# exp31dc.net
KiCad netlist of a schematic drawn in EAGLE
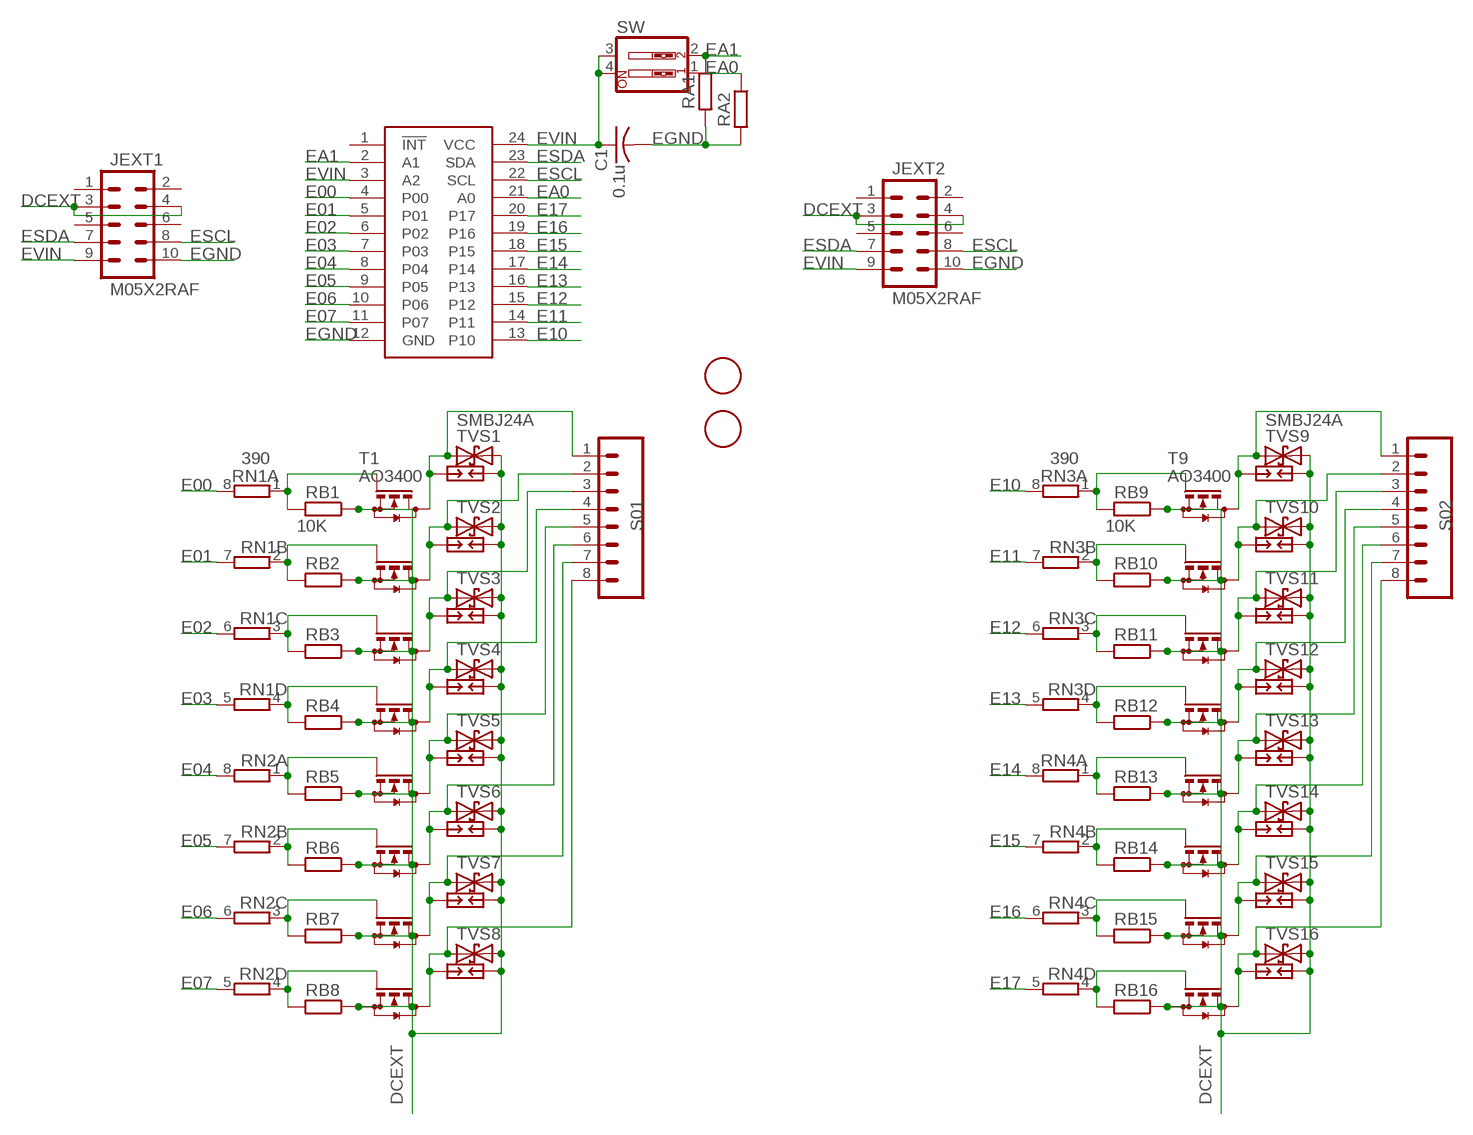
[diagram p0: schematic, sheet 1]

(export (version "E")
  (design (tool "Eeschema 10.0.6"))
  (components
    (comp (ref "C1")
      (value "0.1u")
      (footprint "eagle-import:C0603")
      (libsource (lib "eagle-import") (part "C-USC0603"))
    )
    (comp (ref "JEXT1")
      (value "M05X2RAF")
      (footprint "eagle-import:2X5-RAF")
      (libsource (lib "eagle-import") (part "M05X2RAF"))
    )
    (comp (ref "JEXT2")
      (value "M05X2RAF")
      (footprint "eagle-import:2X5-RAF")
      (libsource (lib "eagle-import") (part "M05X2RAF"))
    )
    (comp (ref "PCA9555")
      (value "PCA9555")
      (footprint "eagle-import:TSSOP24")
      (libsource (lib "eagle-import") (part "PCF8575TSSOP24"))
    )
    (comp (ref "RA1")
      (value "10K")
      (footprint "eagle-import:R0603")
      (libsource (lib "eagle-import") (part "R-EU_R0603"))
    )
    (comp (ref "RA2")
      (value "10K")
      (footprint "eagle-import:R0603")
      (libsource (lib "eagle-import") (part "R-EU_R0603"))
    )
    (comp (ref "RB1")
      (value "10K")
      (footprint "eagle-import:R0603")
      (libsource (lib "eagle-import") (part "R-EU_R0603"))
    )
    (comp (ref "RB2")
      (value "10K")
      (footprint "eagle-import:R0603")
      (libsource (lib "eagle-import") (part "R-EU_R0603"))
    )
    (comp (ref "RB3")
      (value "10K")
      (footprint "eagle-import:R0603")
      (libsource (lib "eagle-import") (part "R-EU_R0603"))
    )
    (comp (ref "RB4")
      (value "10K")
      (footprint "eagle-import:R0603")
      (libsource (lib "eagle-import") (part "R-EU_R0603"))
    )
    (comp (ref "RB5")
      (value "10K")
      (footprint "eagle-import:R0603")
      (libsource (lib "eagle-import") (part "R-EU_R0603"))
    )
    (comp (ref "RB6")
      (value "10K")
      (footprint "eagle-import:R0603")
      (libsource (lib "eagle-import") (part "R-EU_R0603"))
    )
    (comp (ref "RB7")
      (value "10K")
      (footprint "eagle-import:R0603")
      (libsource (lib "eagle-import") (part "R-EU_R0603"))
    )
    (comp (ref "RB8")
      (value "10K")
      (footprint "eagle-import:R0603")
      (libsource (lib "eagle-import") (part "R-EU_R0603"))
    )
    (comp (ref "RB9")
      (value "10K")
      (footprint "eagle-import:R0603")
      (libsource (lib "eagle-import") (part "R-EU_R0603"))
    )
    (comp (ref "RB10")
      (value "10K")
      (footprint "eagle-import:R0603")
      (libsource (lib "eagle-import") (part "R-EU_R0603"))
    )
    (comp (ref "RB11")
      (value "10K")
      (footprint "eagle-import:R0603")
      (libsource (lib "eagle-import") (part "R-EU_R0603"))
    )
    (comp (ref "RB12")
      (value "10K")
      (footprint "eagle-import:R0603")
      (libsource (lib "eagle-import") (part "R-EU_R0603"))
    )
    (comp (ref "RB13")
      (value "10K")
      (footprint "eagle-import:R0603")
      (libsource (lib "eagle-import") (part "R-EU_R0603"))
    )
    (comp (ref "RB14")
      (value "10K")
      (footprint "eagle-import:R0603")
      (libsource (lib "eagle-import") (part "R-EU_R0603"))
    )
    (comp (ref "RB15")
      (value "10K")
      (footprint "eagle-import:R0603")
      (libsource (lib "eagle-import") (part "R-EU_R0603"))
    )
    (comp (ref "RB16")
      (value "10K")
      (footprint "eagle-import:R0603")
      (libsource (lib "eagle-import") (part "R-EU_R0603"))
    )
    (comp (ref "RN1")
      (value "390")
      (footprint "eagle-import:EXB38V")
      (libsource (lib "eagle-import") (part "4R-NEXB38V"))
    )
    (comp (ref "RN2")
      (value "390")
      (footprint "eagle-import:EXB38V")
      (libsource (lib "eagle-import") (part "4R-NEXB38V"))
    )
    (comp (ref "RN3")
      (value "390")
      (footprint "eagle-import:EXB38V")
      (libsource (lib "eagle-import") (part "4R-NEXB38V"))
    )
    (comp (ref "RN4")
      (value "390")
      (footprint "eagle-import:EXB38V")
      (libsource (lib "eagle-import") (part "4R-NEXB38V"))
    )
    (comp (ref "S01")
      (value "M085MM-8")
      (footprint "eagle-import:SCREWTERMINAL-5MM-8")
      (libsource (lib "eagle-import") (part "M085MM-8"))
    )
    (comp (ref "S02")
      (value "M085MM-8")
      (footprint "eagle-import:SCREWTERMINAL-5MM-8")
      (libsource (lib "eagle-import") (part "M085MM-8"))
    )
    (comp (ref "SP1")
      (value "PCB-SGAP")
      (footprint "eagle-import:PCB-SGAP")
      (libsource (lib "eagle-import") (part "PCB-SGAP"))
    )
    (comp (ref "SP2")
      (value "PCB-SGAP")
      (footprint "eagle-import:PCB-SGAP")
      (libsource (lib "eagle-import") (part "PCB-SGAP"))
    )
    (comp (ref "SP3")
      (value "PCB-SGAP")
      (footprint "eagle-import:PCB-SGAP")
      (libsource (lib "eagle-import") (part "PCB-SGAP"))
    )
    (comp (ref "SP4")
      (value "PCB-SGAP")
      (footprint "eagle-import:PCB-SGAP")
      (libsource (lib "eagle-import") (part "PCB-SGAP"))
    )
    (comp (ref "SP5")
      (value "PCB-SGAP")
      (footprint "eagle-import:PCB-SGAP")
      (libsource (lib "eagle-import") (part "PCB-SGAP"))
    )
    (comp (ref "SP6")
      (value "PCB-SGAP")
      (footprint "eagle-import:PCB-SGAP")
      (libsource (lib "eagle-import") (part "PCB-SGAP"))
    )
    (comp (ref "SP7")
      (value "PCB-SGAP")
      (footprint "eagle-import:PCB-SGAP")
      (libsource (lib "eagle-import") (part "PCB-SGAP"))
    )
    (comp (ref "SP8")
      (value "PCB-SGAP")
      (footprint "eagle-import:PCB-SGAP")
      (libsource (lib "eagle-import") (part "PCB-SGAP"))
    )
    (comp (ref "SP9")
      (value "PCB-SGAP")
      (footprint "eagle-import:PCB-SGAP")
      (libsource (lib "eagle-import") (part "PCB-SGAP"))
    )
    (comp (ref "SP10")
      (value "PCB-SGAP")
      (footprint "eagle-import:PCB-SGAP")
      (libsource (lib "eagle-import") (part "PCB-SGAP"))
    )
    (comp (ref "SP11")
      (value "PCB-SGAP")
      (footprint "eagle-import:PCB-SGAP")
      (libsource (lib "eagle-import") (part "PCB-SGAP"))
    )
    (comp (ref "SP12")
      (value "PCB-SGAP")
      (footprint "eagle-import:PCB-SGAP")
      (libsource (lib "eagle-import") (part "PCB-SGAP"))
    )
    (comp (ref "SP13")
      (value "PCB-SGAP")
      (footprint "eagle-import:PCB-SGAP")
      (libsource (lib "eagle-import") (part "PCB-SGAP"))
    )
    (comp (ref "SP14")
      (value "PCB-SGAP")
      (footprint "eagle-import:PCB-SGAP")
      (libsource (lib "eagle-import") (part "PCB-SGAP"))
    )
    (comp (ref "SP15")
      (value "PCB-SGAP")
      (footprint "eagle-import:PCB-SGAP")
      (libsource (lib "eagle-import") (part "PCB-SGAP"))
    )
    (comp (ref "SP16")
      (value "PCB-SGAP")
      (footprint "eagle-import:PCB-SGAP")
      (libsource (lib "eagle-import") (part "PCB-SGAP"))
    )
    (comp (ref "SW")
      (value "SW_DIP-2")
      (footprint "eagle-import:DIPSWITCH-02")
      (libsource (lib "eagle-import") (part "SW_DIP-2"))
    )
    (comp (ref "T1")
      (value "AO3400")
      (footprint "eagle-import:SOT23")
      (libsource (lib "eagle-import") (part "BSS123"))
    )
    (comp (ref "T2")
      (value "AO3400")
      (footprint "eagle-import:SOT23")
      (libsource (lib "eagle-import") (part "BSS123"))
    )
    (comp (ref "T3")
      (value "AO3400")
      (footprint "eagle-import:SOT23")
      (libsource (lib "eagle-import") (part "BSS123"))
    )
    (comp (ref "T4")
      (value "AO3400")
      (footprint "eagle-import:SOT23")
      (libsource (lib "eagle-import") (part "BSS123"))
    )
    (comp (ref "T5")
      (value "AO3400")
      (footprint "eagle-import:SOT23")
      (libsource (lib "eagle-import") (part "BSS123"))
    )
    (comp (ref "T6")
      (value "AO3400")
      (footprint "eagle-import:SOT23")
      (libsource (lib "eagle-import") (part "BSS123"))
    )
    (comp (ref "T7")
      (value "AO3400")
      (footprint "eagle-import:SOT23")
      (libsource (lib "eagle-import") (part "BSS123"))
    )
    (comp (ref "T8")
      (value "AO3400")
      (footprint "eagle-import:SOT23")
      (libsource (lib "eagle-import") (part "BSS123"))
    )
    (comp (ref "T9")
      (value "AO3400")
      (footprint "eagle-import:SOT23")
      (libsource (lib "eagle-import") (part "BSS123"))
    )
    (comp (ref "T10")
      (value "AO3400")
      (footprint "eagle-import:SOT23")
      (libsource (lib "eagle-import") (part "BSS123"))
    )
    (comp (ref "T11")
      (value "AO3400")
      (footprint "eagle-import:SOT23")
      (libsource (lib "eagle-import") (part "BSS123"))
    )
    (comp (ref "T12")
      (value "AO3400")
      (footprint "eagle-import:SOT23")
      (libsource (lib "eagle-import") (part "BSS123"))
    )
    (comp (ref "T13")
      (value "AO3400")
      (footprint "eagle-import:SOT23")
      (libsource (lib "eagle-import") (part "BSS123"))
    )
    (comp (ref "T14")
      (value "AO3400")
      (footprint "eagle-import:SOT23")
      (libsource (lib "eagle-import") (part "BSS123"))
    )
    (comp (ref "T15")
      (value "AO3400")
      (footprint "eagle-import:SOT23")
      (libsource (lib "eagle-import") (part "BSS123"))
    )
    (comp (ref "T16")
      (value "AO3400")
      (footprint "eagle-import:SOT23")
      (libsource (lib "eagle-import") (part "BSS123"))
    )
    (comp (ref "TVS1")
      (value "SMBJ24A")
      (footprint "eagle-import:SMB")
      (libsource (lib "eagle-import") (part "TVSSMB"))
    )
    (comp (ref "TVS2")
      (value "SMBJ24A")
      (footprint "eagle-import:SMB")
      (libsource (lib "eagle-import") (part "TVSSMB"))
    )
    (comp (ref "TVS3")
      (value "SMBJ24A")
      (footprint "eagle-import:SMB")
      (libsource (lib "eagle-import") (part "TVSSMB"))
    )
    (comp (ref "TVS4")
      (value "SMBJ24A")
      (footprint "eagle-import:SMB")
      (libsource (lib "eagle-import") (part "TVSSMB"))
    )
    (comp (ref "TVS5")
      (value "SMBJ24A")
      (footprint "eagle-import:SMB")
      (libsource (lib "eagle-import") (part "TVSSMB"))
    )
    (comp (ref "TVS6")
      (value "SMBJ24A")
      (footprint "eagle-import:SMB")
      (libsource (lib "eagle-import") (part "TVSSMB"))
    )
    (comp (ref "TVS7")
      (value "SMBJ24A")
      (footprint "eagle-import:SMB")
      (libsource (lib "eagle-import") (part "TVSSMB"))
    )
    (comp (ref "TVS8")
      (value "SMBJ24A")
      (footprint "eagle-import:SMB")
      (libsource (lib "eagle-import") (part "TVSSMB"))
    )
    (comp (ref "TVS9")
      (value "SMBJ24A")
      (footprint "eagle-import:SMB")
      (libsource (lib "eagle-import") (part "TVSSMB"))
    )
    (comp (ref "TVS10")
      (value "SMBJ24A")
      (footprint "eagle-import:SMB")
      (libsource (lib "eagle-import") (part "TVSSMB"))
    )
    (comp (ref "TVS11")
      (value "SMBJ24A")
      (footprint "eagle-import:SMB")
      (libsource (lib "eagle-import") (part "TVSSMB"))
    )
    (comp (ref "TVS12")
      (value "SMBJ24A")
      (footprint "eagle-import:SMB")
      (libsource (lib "eagle-import") (part "TVSSMB"))
    )
    (comp (ref "TVS13")
      (value "SMBJ24A")
      (footprint "eagle-import:SMB")
      (libsource (lib "eagle-import") (part "TVSSMB"))
    )
    (comp (ref "TVS14")
      (value "SMBJ24A")
      (footprint "eagle-import:SMB")
      (libsource (lib "eagle-import") (part "TVSSMB"))
    )
    (comp (ref "TVS15")
      (value "SMBJ24A")
      (footprint "eagle-import:SMB")
      (libsource (lib "eagle-import") (part "TVSSMB"))
    )
    (comp (ref "TVS16")
      (value "SMBJ24A")
      (footprint "eagle-import:SMB")
      (libsource (lib "eagle-import") (part "TVSSMB"))
    )
    (comp (ref "U$1")
      (value "FIDUCIAL")
      (footprint "eagle-import:FIDUCIAL_1MM")
      (libsource (lib "eagle-import") (part "FIDUCIAL"))
    )
    (comp (ref "U$2")
      (value "FIDUCIAL")
      (footprint "eagle-import:FIDUCIAL_1MM")
      (libsource (lib "eagle-import") (part "FIDUCIAL"))
    )
  )
  (nets
    (net (code "1") (name "/DCEXT") (class "Default")
      (node (ref "JEXT1") (pin "3") (pinfunction "3_3") (pintype "passive"))
      (node (ref "JEXT1") (pin "4") (pinfunction "4_4") (pintype "passive"))
      (node (ref "JEXT2") (pin "3") (pinfunction "3_3") (pintype "passive"))
      (node (ref "JEXT2") (pin "4") (pinfunction "4_4") (pintype "passive"))
      (node (ref "RB1") (pin "1") (pinfunction "1_1") (pintype "passive"))
      (node (ref "RB10") (pin "1") (pinfunction "1_1") (pintype "passive"))
      (node (ref "RB11") (pin "1") (pinfunction "1_1") (pintype "passive"))
      (node (ref "RB12") (pin "1") (pinfunction "1_1") (pintype "passive"))
      (node (ref "RB13") (pin "1") (pinfunction "1_1") (pintype "passive"))
      (node (ref "RB14") (pin "1") (pinfunction "1_1") (pintype "passive"))
      (node (ref "RB15") (pin "1") (pinfunction "1_1") (pintype "passive"))
      (node (ref "RB16") (pin "1") (pinfunction "1_1") (pintype "passive"))
      (node (ref "RB2") (pin "1") (pinfunction "1_1") (pintype "passive"))
      (node (ref "RB3") (pin "1") (pinfunction "1_1") (pintype "passive"))
      (node (ref "RB4") (pin "1") (pinfunction "1_1") (pintype "passive"))
      (node (ref "RB5") (pin "1") (pinfunction "1_1") (pintype "passive"))
      (node (ref "RB6") (pin "1") (pinfunction "1_1") (pintype "passive"))
      (node (ref "RB7") (pin "1") (pinfunction "1_1") (pintype "passive"))
      (node (ref "RB8") (pin "1") (pinfunction "1_1") (pintype "passive"))
      (node (ref "RB9") (pin "1") (pinfunction "1_1") (pintype "passive"))
      (node (ref "SP1") (pin "1") (pinfunction "1_1") (pintype "passive"))
      (node (ref "SP10") (pin "1") (pinfunction "1_1") (pintype "passive"))
      (node (ref "SP11") (pin "1") (pinfunction "1_1") (pintype "passive"))
      (node (ref "SP12") (pin "1") (pinfunction "1_1") (pintype "passive"))
      (node (ref "SP13") (pin "1") (pinfunction "1_1") (pintype "passive"))
      (node (ref "SP14") (pin "1") (pinfunction "1_1") (pintype "passive"))
      (node (ref "SP15") (pin "1") (pinfunction "1_1") (pintype "passive"))
      (node (ref "SP16") (pin "1") (pinfunction "1_1") (pintype "passive"))
      (node (ref "SP2") (pin "1") (pinfunction "1_1") (pintype "passive"))
      (node (ref "SP3") (pin "1") (pinfunction "1_1") (pintype "passive"))
      (node (ref "SP4") (pin "1") (pinfunction "1_1") (pintype "passive"))
      (node (ref "SP5") (pin "1") (pinfunction "1_1") (pintype "passive"))
      (node (ref "SP6") (pin "1") (pinfunction "1_1") (pintype "passive"))
      (node (ref "SP7") (pin "1") (pinfunction "1_1") (pintype "passive"))
      (node (ref "SP8") (pin "1") (pinfunction "1_1") (pintype "passive"))
      (node (ref "SP9") (pin "1") (pinfunction "1_1") (pintype "passive"))
      (node (ref "T1") (pin "2") (pinfunction "S_2") (pintype "passive"))
      (node (ref "T10") (pin "2") (pinfunction "S_2") (pintype "passive"))
      (node (ref "T11") (pin "2") (pinfunction "S_2") (pintype "passive"))
      (node (ref "T12") (pin "2") (pinfunction "S_2") (pintype "passive"))
      (node (ref "T13") (pin "2") (pinfunction "S_2") (pintype "passive"))
      (node (ref "T14") (pin "2") (pinfunction "S_2") (pintype "passive"))
      (node (ref "T15") (pin "2") (pinfunction "S_2") (pintype "passive"))
      (node (ref "T16") (pin "2") (pinfunction "S_2") (pintype "passive"))
      (node (ref "T2") (pin "2") (pinfunction "S_2") (pintype "passive"))
      (node (ref "T3") (pin "2") (pinfunction "S_2") (pintype "passive"))
      (node (ref "T4") (pin "2") (pinfunction "S_2") (pintype "passive"))
      (node (ref "T5") (pin "2") (pinfunction "S_2") (pintype "passive"))
      (node (ref "T6") (pin "2") (pinfunction "S_2") (pintype "passive"))
      (node (ref "T7") (pin "2") (pinfunction "S_2") (pintype "passive"))
      (node (ref "T8") (pin "2") (pinfunction "S_2") (pintype "passive"))
      (node (ref "T9") (pin "2") (pinfunction "S_2") (pintype "passive"))
      (node (ref "TVS1") (pin "C") (pinfunction "C_C") (pintype "passive"))
      (node (ref "TVS10") (pin "C") (pinfunction "C_C") (pintype "passive"))
      (node (ref "TVS11") (pin "C") (pinfunction "C_C") (pintype "passive"))
      (node (ref "TVS12") (pin "C") (pinfunction "C_C") (pintype "passive"))
      (node (ref "TVS13") (pin "C") (pinfunction "C_C") (pintype "passive"))
      (node (ref "TVS14") (pin "C") (pinfunction "C_C") (pintype "passive"))
      (node (ref "TVS15") (pin "C") (pinfunction "C_C") (pintype "passive"))
      (node (ref "TVS16") (pin "C") (pinfunction "C_C") (pintype "passive"))
      (node (ref "TVS2") (pin "C") (pinfunction "C_C") (pintype "passive"))
      (node (ref "TVS3") (pin "C") (pinfunction "C_C") (pintype "passive"))
      (node (ref "TVS4") (pin "C") (pinfunction "C_C") (pintype "passive"))
      (node (ref "TVS5") (pin "C") (pinfunction "C_C") (pintype "passive"))
      (node (ref "TVS6") (pin "C") (pinfunction "C_C") (pintype "passive"))
      (node (ref "TVS7") (pin "C") (pinfunction "C_C") (pintype "passive"))
      (node (ref "TVS8") (pin "C") (pinfunction "C_C") (pintype "passive"))
      (node (ref "TVS9") (pin "C") (pinfunction "C_C") (pintype "passive"))
    )
    (net (code "2") (name "/E00") (class "Default")
      (node (ref "PCA9555") (pin "4") (pinfunction "P00_4") (pintype "bidirectional"))
      (node (ref "RN1") (pin "8") (pinfunction "2_8") (pintype "passive"))
    )
    (net (code "3") (name "/E01") (class "Default")
      (node (ref "PCA9555") (pin "5") (pinfunction "P01_5") (pintype "bidirectional"))
      (node (ref "RN1") (pin "7") (pinfunction "2_7") (pintype "passive"))
    )
    (net (code "4") (name "/E02") (class "Default")
      (node (ref "PCA9555") (pin "6") (pinfunction "P02_6") (pintype "bidirectional"))
      (node (ref "RN1") (pin "6") (pinfunction "2_6") (pintype "passive"))
    )
    (net (code "5") (name "/E03") (class "Default")
      (node (ref "PCA9555") (pin "7") (pinfunction "P03_7") (pintype "bidirectional"))
      (node (ref "RN1") (pin "5") (pinfunction "2_5") (pintype "passive"))
    )
    (net (code "6") (name "/E04") (class "Default")
      (node (ref "PCA9555") (pin "8") (pinfunction "P04_8") (pintype "bidirectional"))
      (node (ref "RN2") (pin "8") (pinfunction "2_8") (pintype "passive"))
    )
    (net (code "7") (name "/E05") (class "Default")
      (node (ref "PCA9555") (pin "9") (pinfunction "P05_9") (pintype "bidirectional"))
      (node (ref "RN2") (pin "7") (pinfunction "2_7") (pintype "passive"))
    )
    (net (code "8") (name "/E06") (class "Default")
      (node (ref "PCA9555") (pin "10") (pinfunction "P06_10") (pintype "bidirectional"))
      (node (ref "RN2") (pin "6") (pinfunction "2_6") (pintype "passive"))
    )
    (net (code "9") (name "/E07") (class "Default")
      (node (ref "PCA9555") (pin "11") (pinfunction "P07_11") (pintype "bidirectional"))
      (node (ref "RN2") (pin "5") (pinfunction "2_5") (pintype "passive"))
    )
    (net (code "10") (name "/E10") (class "Default")
      (node (ref "PCA9555") (pin "13") (pinfunction "P10_13") (pintype "bidirectional"))
      (node (ref "RN3") (pin "8") (pinfunction "2_8") (pintype "passive"))
    )
    (net (code "11") (name "/E11") (class "Default")
      (node (ref "PCA9555") (pin "14") (pinfunction "P11_14") (pintype "bidirectional"))
      (node (ref "RN3") (pin "7") (pinfunction "2_7") (pintype "passive"))
    )
    (net (code "12") (name "/E12") (class "Default")
      (node (ref "PCA9555") (pin "15") (pinfunction "P12_15") (pintype "bidirectional"))
      (node (ref "RN3") (pin "6") (pinfunction "2_6") (pintype "passive"))
    )
    (net (code "13") (name "/E13") (class "Default")
      (node (ref "PCA9555") (pin "16") (pinfunction "P13_16") (pintype "bidirectional"))
      (node (ref "RN3") (pin "5") (pinfunction "2_5") (pintype "passive"))
    )
    (net (code "14") (name "/E14") (class "Default")
      (node (ref "PCA9555") (pin "17") (pinfunction "P14_17") (pintype "bidirectional"))
      (node (ref "RN4") (pin "8") (pinfunction "2_8") (pintype "passive"))
    )
    (net (code "15") (name "/E15") (class "Default")
      (node (ref "PCA9555") (pin "18") (pinfunction "P15_18") (pintype "bidirectional"))
      (node (ref "RN4") (pin "7") (pinfunction "2_7") (pintype "passive"))
    )
    (net (code "16") (name "/E16") (class "Default")
      (node (ref "PCA9555") (pin "19") (pinfunction "P16_19") (pintype "bidirectional"))
      (node (ref "RN4") (pin "6") (pinfunction "2_6") (pintype "passive"))
    )
    (net (code "17") (name "/E17") (class "Default")
      (node (ref "PCA9555") (pin "20") (pinfunction "P17_20") (pintype "bidirectional"))
      (node (ref "RN4") (pin "5") (pinfunction "2_5") (pintype "passive"))
    )
    (net (code "18") (name "/EA0") (class "Default")
      (node (ref "PCA9555") (pin "21") (pinfunction "A0_21") (pintype "bidirectional"))
      (node (ref "RA2") (pin "1") (pinfunction "1_1") (pintype "passive"))
      (node (ref "SW") (pin "1") (pinfunction "1_1") (pintype "passive"))
    )
    (net (code "19") (name "/EA1") (class "Default")
      (node (ref "PCA9555") (pin "2") (pinfunction "A1_2") (pintype "bidirectional"))
      (node (ref "RA1") (pin "1") (pinfunction "1_1") (pintype "passive"))
      (node (ref "SW") (pin "2") (pinfunction "2_2") (pintype "passive"))
    )
    (net (code "20") (name "/EGND") (class "Default")
      (node (ref "C1") (pin "2") (pinfunction "2_2") (pintype "passive"))
      (node (ref "JEXT1") (pin "10") (pinfunction "10_10") (pintype "passive"))
      (node (ref "JEXT2") (pin "10") (pinfunction "10_10") (pintype "passive"))
      (node (ref "PCA9555") (pin "12") (pinfunction "GND_12") (pintype "power_in"))
      (node (ref "RA1") (pin "2") (pinfunction "2_2") (pintype "passive"))
      (node (ref "RA2") (pin "2") (pinfunction "2_2") (pintype "passive"))
    )
    (net (code "21") (name "/ESCL") (class "Default")
      (node (ref "JEXT1") (pin "8") (pinfunction "8_8") (pintype "passive"))
      (node (ref "JEXT2") (pin "8") (pinfunction "8_8") (pintype "passive"))
      (node (ref "PCA9555") (pin "22") (pinfunction "SCL_22") (pintype "bidirectional"))
    )
    (net (code "22") (name "/ESDA") (class "Default")
      (node (ref "JEXT1") (pin "7") (pinfunction "7_7") (pintype "passive"))
      (node (ref "JEXT2") (pin "7") (pinfunction "7_7") (pintype "passive"))
      (node (ref "PCA9555") (pin "23") (pinfunction "SDA_23") (pintype "bidirectional"))
    )
    (net (code "23") (name "/EVIN") (class "Default")
      (node (ref "C1") (pin "1") (pinfunction "1_1") (pintype "passive"))
      (node (ref "JEXT1") (pin "9") (pinfunction "9_9") (pintype "passive"))
      (node (ref "JEXT2") (pin "9") (pinfunction "9_9") (pintype "passive"))
      (node (ref "PCA9555") (pin "24") (pinfunction "VCC_24") (pintype "power_in"))
      (node (ref "PCA9555") (pin "3") (pinfunction "A2_3") (pintype "bidirectional"))
      (node (ref "SW") (pin "3") (pinfunction "3_3") (pintype "passive"))
      (node (ref "SW") (pin "4") (pinfunction "4_4") (pintype "passive"))
    )
    (net (code "24") (name "Net-(RN1B-1)") (class "Default")
      (node (ref "RB2") (pin "2") (pinfunction "2_2") (pintype "passive"))
      (node (ref "RN1") (pin "2") (pinfunction "1_2") (pintype "passive"))
      (node (ref "T2") (pin "1") (pinfunction "G_1") (pintype "passive"))
    )
    (net (code "25") (name "Net-(RN1C-1)") (class "Default")
      (node (ref "RB3") (pin "2") (pinfunction "2_2") (pintype "passive"))
      (node (ref "RN1") (pin "3") (pinfunction "1_3") (pintype "passive"))
      (node (ref "T3") (pin "1") (pinfunction "G_1") (pintype "passive"))
    )
    (net (code "26") (name "Net-(RN1D-1)") (class "Default")
      (node (ref "RB4") (pin "2") (pinfunction "2_2") (pintype "passive"))
      (node (ref "RN1") (pin "4") (pinfunction "1_4") (pintype "passive"))
      (node (ref "T4") (pin "1") (pinfunction "G_1") (pintype "passive"))
    )
    (net (code "27") (name "Net-(RN2B-1)") (class "Default")
      (node (ref "RB6") (pin "2") (pinfunction "2_2") (pintype "passive"))
      (node (ref "RN2") (pin "2") (pinfunction "1_2") (pintype "passive"))
      (node (ref "T6") (pin "1") (pinfunction "G_1") (pintype "passive"))
    )
    (net (code "28") (name "Net-(RN2C-1)") (class "Default")
      (node (ref "RB7") (pin "2") (pinfunction "2_2") (pintype "passive"))
      (node (ref "RN2") (pin "3") (pinfunction "1_3") (pintype "passive"))
      (node (ref "T7") (pin "1") (pinfunction "G_1") (pintype "passive"))
    )
    (net (code "29") (name "Net-(RN2D-1)") (class "Default")
      (node (ref "RB8") (pin "2") (pinfunction "2_2") (pintype "passive"))
      (node (ref "RN2") (pin "4") (pinfunction "1_4") (pintype "passive"))
      (node (ref "T8") (pin "1") (pinfunction "G_1") (pintype "passive"))
    )
    (net (code "30") (name "Net-(RN3B-1)") (class "Default")
      (node (ref "RB10") (pin "2") (pinfunction "2_2") (pintype "passive"))
      (node (ref "RN3") (pin "2") (pinfunction "1_2") (pintype "passive"))
      (node (ref "T10") (pin "1") (pinfunction "G_1") (pintype "passive"))
    )
    (net (code "31") (name "Net-(RN3C-1)") (class "Default")
      (node (ref "RB11") (pin "2") (pinfunction "2_2") (pintype "passive"))
      (node (ref "RN3") (pin "3") (pinfunction "1_3") (pintype "passive"))
      (node (ref "T11") (pin "1") (pinfunction "G_1") (pintype "passive"))
    )
    (net (code "32") (name "Net-(RN3D-1)") (class "Default")
      (node (ref "RB12") (pin "2") (pinfunction "2_2") (pintype "passive"))
      (node (ref "RN3") (pin "4") (pinfunction "1_4") (pintype "passive"))
      (node (ref "T12") (pin "1") (pinfunction "G_1") (pintype "passive"))
    )
    (net (code "33") (name "Net-(RN4B-1)") (class "Default")
      (node (ref "RB14") (pin "2") (pinfunction "2_2") (pintype "passive"))
      (node (ref "RN4") (pin "2") (pinfunction "1_2") (pintype "passive"))
      (node (ref "T14") (pin "1") (pinfunction "G_1") (pintype "passive"))
    )
    (net (code "34") (name "Net-(RN4C-1)") (class "Default")
      (node (ref "RB15") (pin "2") (pinfunction "2_2") (pintype "passive"))
      (node (ref "RN4") (pin "3") (pinfunction "1_3") (pintype "passive"))
      (node (ref "T15") (pin "1") (pinfunction "G_1") (pintype "passive"))
    )
    (net (code "35") (name "Net-(RN4D-1)") (class "Default")
      (node (ref "RB16") (pin "2") (pinfunction "2_2") (pintype "passive"))
      (node (ref "RN4") (pin "4") (pinfunction "1_4") (pintype "passive"))
      (node (ref "T16") (pin "1") (pinfunction "G_1") (pintype "passive"))
    )
    (net (code "36") (name "Net-(T1-D)") (class "Default")
      (node (ref "S01") (pin "1") (pinfunction "1_1") (pintype "passive"))
      (node (ref "SP1") (pin "2") (pinfunction "2_2") (pintype "passive"))
      (node (ref "T1") (pin "3") (pinfunction "D_3") (pintype "passive"))
      (node (ref "TVS1") (pin "A") (pinfunction "A_A") (pintype "passive"))
    )
    (net (code "37") (name "Net-(T1-G)") (class "Default")
      (node (ref "RB1") (pin "2") (pinfunction "2_2") (pintype "passive"))
      (node (ref "RN1") (pin "1") (pinfunction "1_1") (pintype "passive"))
      (node (ref "T1") (pin "1") (pinfunction "G_1") (pintype "passive"))
    )
    (net (code "38") (name "Net-(T2-D)") (class "Default")
      (node (ref "S01") (pin "2") (pinfunction "2_2") (pintype "passive"))
      (node (ref "SP2") (pin "2") (pinfunction "2_2") (pintype "passive"))
      (node (ref "T2") (pin "3") (pinfunction "D_3") (pintype "passive"))
      (node (ref "TVS2") (pin "A") (pinfunction "A_A") (pintype "passive"))
    )
    (net (code "39") (name "Net-(T3-D)") (class "Default")
      (node (ref "S01") (pin "3") (pinfunction "3_3") (pintype "passive"))
      (node (ref "SP3") (pin "2") (pinfunction "2_2") (pintype "passive"))
      (node (ref "T3") (pin "3") (pinfunction "D_3") (pintype "passive"))
      (node (ref "TVS3") (pin "A") (pinfunction "A_A") (pintype "passive"))
    )
    (net (code "40") (name "Net-(T4-D)") (class "Default")
      (node (ref "S01") (pin "4") (pinfunction "4_4") (pintype "passive"))
      (node (ref "SP4") (pin "2") (pinfunction "2_2") (pintype "passive"))
      (node (ref "T4") (pin "3") (pinfunction "D_3") (pintype "passive"))
      (node (ref "TVS4") (pin "A") (pinfunction "A_A") (pintype "passive"))
    )
    (net (code "41") (name "Net-(T5-D)") (class "Default")
      (node (ref "S01") (pin "5") (pinfunction "5_5") (pintype "passive"))
      (node (ref "SP5") (pin "2") (pinfunction "2_2") (pintype "passive"))
      (node (ref "T5") (pin "3") (pinfunction "D_3") (pintype "passive"))
      (node (ref "TVS5") (pin "A") (pinfunction "A_A") (pintype "passive"))
    )
    (net (code "42") (name "Net-(T5-G)") (class "Default")
      (node (ref "RB5") (pin "2") (pinfunction "2_2") (pintype "passive"))
      (node (ref "RN2") (pin "1") (pinfunction "1_1") (pintype "passive"))
      (node (ref "T5") (pin "1") (pinfunction "G_1") (pintype "passive"))
    )
    (net (code "43") (name "Net-(T6-D)") (class "Default")
      (node (ref "S01") (pin "6") (pinfunction "6_6") (pintype "passive"))
      (node (ref "SP6") (pin "2") (pinfunction "2_2") (pintype "passive"))
      (node (ref "T6") (pin "3") (pinfunction "D_3") (pintype "passive"))
      (node (ref "TVS6") (pin "A") (pinfunction "A_A") (pintype "passive"))
    )
    (net (code "44") (name "Net-(T7-D)") (class "Default")
      (node (ref "S01") (pin "7") (pinfunction "7_7") (pintype "passive"))
      (node (ref "SP7") (pin "2") (pinfunction "2_2") (pintype "passive"))
      (node (ref "T7") (pin "3") (pinfunction "D_3") (pintype "passive"))
      (node (ref "TVS7") (pin "A") (pinfunction "A_A") (pintype "passive"))
    )
    (net (code "45") (name "Net-(T8-D)") (class "Default")
      (node (ref "S01") (pin "8") (pinfunction "8_8") (pintype "passive"))
      (node (ref "SP8") (pin "2") (pinfunction "2_2") (pintype "passive"))
      (node (ref "T8") (pin "3") (pinfunction "D_3") (pintype "passive"))
      (node (ref "TVS8") (pin "A") (pinfunction "A_A") (pintype "passive"))
    )
    (net (code "46") (name "Net-(T9-D)") (class "Default")
      (node (ref "S02") (pin "1") (pinfunction "1_1") (pintype "passive"))
      (node (ref "SP9") (pin "2") (pinfunction "2_2") (pintype "passive"))
      (node (ref "T9") (pin "3") (pinfunction "D_3") (pintype "passive"))
      (node (ref "TVS9") (pin "A") (pinfunction "A_A") (pintype "passive"))
    )
    (net (code "47") (name "Net-(T9-G)") (class "Default")
      (node (ref "RB9") (pin "2") (pinfunction "2_2") (pintype "passive"))
      (node (ref "RN3") (pin "1") (pinfunction "1_1") (pintype "passive"))
      (node (ref "T9") (pin "1") (pinfunction "G_1") (pintype "passive"))
    )
    (net (code "48") (name "Net-(T10-D)") (class "Default")
      (node (ref "S02") (pin "2") (pinfunction "2_2") (pintype "passive"))
      (node (ref "SP10") (pin "2") (pinfunction "2_2") (pintype "passive"))
      (node (ref "T10") (pin "3") (pinfunction "D_3") (pintype "passive"))
      (node (ref "TVS10") (pin "A") (pinfunction "A_A") (pintype "passive"))
    )
    (net (code "49") (name "Net-(T11-D)") (class "Default")
      (node (ref "S02") (pin "3") (pinfunction "3_3") (pintype "passive"))
      (node (ref "SP11") (pin "2") (pinfunction "2_2") (pintype "passive"))
      (node (ref "T11") (pin "3") (pinfunction "D_3") (pintype "passive"))
      (node (ref "TVS11") (pin "A") (pinfunction "A_A") (pintype "passive"))
    )
    (net (code "50") (name "Net-(T12-D)") (class "Default")
      (node (ref "S02") (pin "4") (pinfunction "4_4") (pintype "passive"))
      (node (ref "SP12") (pin "2") (pinfunction "2_2") (pintype "passive"))
      (node (ref "T12") (pin "3") (pinfunction "D_3") (pintype "passive"))
      (node (ref "TVS12") (pin "A") (pinfunction "A_A") (pintype "passive"))
    )
    (net (code "51") (name "Net-(T13-D)") (class "Default")
      (node (ref "S02") (pin "5") (pinfunction "5_5") (pintype "passive"))
      (node (ref "SP13") (pin "2") (pinfunction "2_2") (pintype "passive"))
      (node (ref "T13") (pin "3") (pinfunction "D_3") (pintype "passive"))
      (node (ref "TVS13") (pin "A") (pinfunction "A_A") (pintype "passive"))
    )
    (net (code "52") (name "Net-(T13-G)") (class "Default")
      (node (ref "RB13") (pin "2") (pinfunction "2_2") (pintype "passive"))
      (node (ref "RN4") (pin "1") (pinfunction "1_1") (pintype "passive"))
      (node (ref "T13") (pin "1") (pinfunction "G_1") (pintype "passive"))
    )
    (net (code "53") (name "Net-(T14-D)") (class "Default")
      (node (ref "S02") (pin "6") (pinfunction "6_6") (pintype "passive"))
      (node (ref "SP14") (pin "2") (pinfunction "2_2") (pintype "passive"))
      (node (ref "T14") (pin "3") (pinfunction "D_3") (pintype "passive"))
      (node (ref "TVS14") (pin "A") (pinfunction "A_A") (pintype "passive"))
    )
    (net (code "54") (name "Net-(T15-D)") (class "Default")
      (node (ref "S02") (pin "7") (pinfunction "7_7") (pintype "passive"))
      (node (ref "SP15") (pin "2") (pinfunction "2_2") (pintype "passive"))
      (node (ref "T15") (pin "3") (pinfunction "D_3") (pintype "passive"))
      (node (ref "TVS15") (pin "A") (pinfunction "A_A") (pintype "passive"))
    )
    (net (code "55") (name "Net-(T16-D)") (class "Default")
      (node (ref "S02") (pin "8") (pinfunction "8_8") (pintype "passive"))
      (node (ref "SP16") (pin "2") (pinfunction "2_2") (pintype "passive"))
      (node (ref "T16") (pin "3") (pinfunction "D_3") (pintype "passive"))
      (node (ref "TVS16") (pin "A") (pinfunction "A_A") (pintype "passive"))
    )
    (net (code "56") (name "unconnected-(JEXT1-Pad1)") (class "Default")
      (node (ref "JEXT1") (pin "1") (pinfunction "1_1") (pintype "passive"))
    )
    (net (code "57") (name "unconnected-(JEXT1-Pad2)") (class "Default")
      (node (ref "JEXT1") (pin "2") (pinfunction "2_2") (pintype "passive"))
    )
    (net (code "58") (name "unconnected-(JEXT1-Pad5)") (class "Default")
      (node (ref "JEXT1") (pin "5") (pinfunction "5_5") (pintype "passive"))
    )
    (net (code "59") (name "unconnected-(JEXT1-Pad6)") (class "Default")
      (node (ref "JEXT1") (pin "6") (pinfunction "6_6") (pintype "passive"))
    )
    (net (code "60") (name "unconnected-(JEXT2-Pad1)") (class "Default")
      (node (ref "JEXT2") (pin "1") (pinfunction "1_1") (pintype "passive"))
    )
    (net (code "61") (name "unconnected-(JEXT2-Pad2)") (class "Default")
      (node (ref "JEXT2") (pin "2") (pinfunction "2_2") (pintype "passive"))
    )
    (net (code "62") (name "unconnected-(JEXT2-Pad5)") (class "Default")
      (node (ref "JEXT2") (pin "5") (pinfunction "5_5") (pintype "passive"))
    )
    (net (code "63") (name "unconnected-(JEXT2-Pad6)") (class "Default")
      (node (ref "JEXT2") (pin "6") (pinfunction "6_6") (pintype "passive"))
    )
    (net (code "64") (name "unconnected-(PCA9555-~{INT}-Pad1)") (class "Default")
      (node (ref "PCA9555") (pin "1") (pinfunction "~{INT}_1") (pintype "bidirectional"))
    )
  )
)
